# tritiled22_cr2354_lux_c.net
KiCad netlist of a schematic drawn in EAGLE
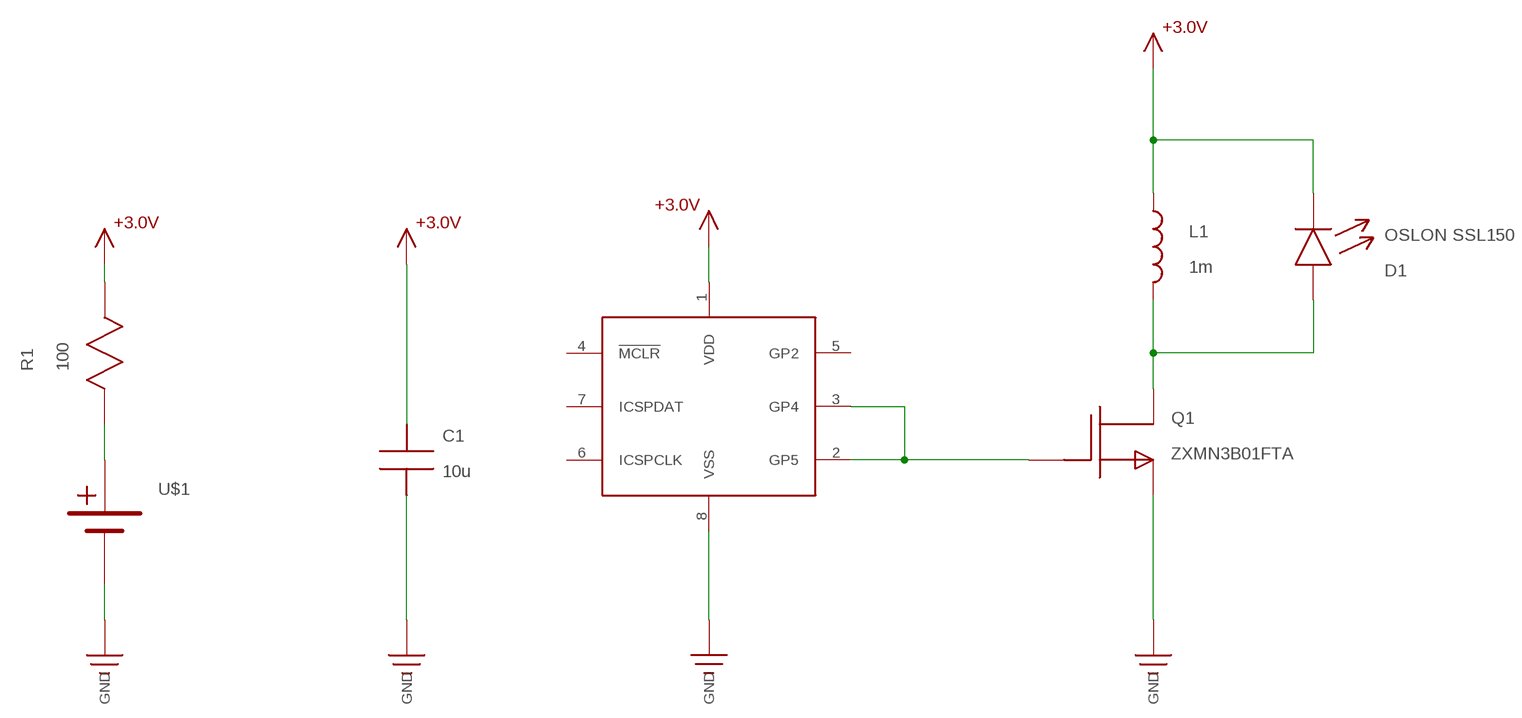
[diagram p0: schematic, sheet 1]

(export (version "E")
  (design (tool "Eeschema 10.0.6"))
  (components
    (comp (ref "C1")
      (value "10u")
      (footprint "eagle-import:1206")
      (libsource (lib "eagle-import") (part "C1206"))
    )
    (comp (ref "D1")
      (value "OSLON SSL150")
      (footprint "eagle-import:LUXEON_C")
      (libsource (lib "eagle-import") (part "LEDLUXEON_C"))
    )
    (comp (ref "L1")
      (value "1m")
      (footprint "eagle-import:SRR6028_INDUCTOR")
      (libsource (lib "eagle-import") (part "SRR6028_INDUCTOR"))
    )
    (comp (ref "Q1")
      (value "ZXMN3B01FTA")
      (footprint "eagle-import:SOT-23")
      (libsource (lib "eagle-import") (part "ZXMN3B01FSOT23"))
    )
    (comp (ref "R1")
      (value "100")
      (footprint "eagle-import:R1206")
      (libsource (lib "eagle-import") (part "R1206"))
    )
    (comp (ref "U$1")
      (value "CR2354_TABBED")
      (footprint "eagle-import:CR2354_TABBED")
      (libsource (lib "eagle-import") (part "CR2354_TABBED"))
    )
    (comp (ref "U1")
      (value "PIC12LF1571")
      (footprint "eagle-import:SOIC8")
      (libsource (lib "eagle-import") (part "PIC12LF1571"))
    )
  )
  (nets
    (net (code "1") (name "+3.0V") (class "Default")
      (node (ref "C1") (pin "P$1") (pinfunction "P$1_P$1") (pintype "bidirectional"))
      (node (ref "D1") (pin "C") (pinfunction "C_C") (pintype "bidirectional"))
      (node (ref "L1") (pin "P$1") (pinfunction "1_P$1") (pintype "passive"))
      (node (ref "R1") (pin "P$2") (pinfunction "P$2_P$2") (pintype "bidirectional"))
      (node (ref "U1") (pin "1") (pinfunction "VDD_1") (pintype "bidirectional"))
    )
    (net (code "2") (name "GND") (class "Default")
      (node (ref "C1") (pin "P$2") (pinfunction "P$2_P$2") (pintype "bidirectional"))
      (node (ref "Q1") (pin "2") (pinfunction "S_2") (pintype "bidirectional"))
      (node (ref "U$1") (pin "GND") (pinfunction "0V_GND") (pintype "power_in"))
      (node (ref "U1") (pin "8") (pinfunction "VSS_8") (pintype "bidirectional"))
    )
    (net (code "3") (name "Net-(L1-2)") (class "Default")
      (node (ref "D1") (pin "A") (pinfunction "A_A") (pintype "bidirectional"))
      (node (ref "L1") (pin "P$2") (pinfunction "2_P$2") (pintype "passive"))
      (node (ref "Q1") (pin "3") (pinfunction "D_3") (pintype "bidirectional"))
    )
    (net (code "4") (name "Net-(Q1-G)") (class "Default")
      (node (ref "Q1") (pin "1") (pinfunction "G_1") (pintype "bidirectional"))
      (node (ref "U1") (pin "2") (pinfunction "GP5_2") (pintype "bidirectional"))
      (node (ref "U1") (pin "3") (pinfunction "GP4_3") (pintype "bidirectional"))
    )
    (net (code "5") (name "Net-(U$1-+V)") (class "Default")
      (node (ref "R1") (pin "P$1") (pinfunction "P$1_P$1") (pintype "bidirectional"))
      (node (ref "U$1") (pin "+3V") (pinfunction "+V_+3V") (pintype "power_in"))
    )
    (net (code "6") (name "unconnected-(U1-GP2-Pad5)") (class "Default")
      (node (ref "U1") (pin "5") (pinfunction "GP2_5") (pintype "bidirectional"))
    )
    (net (code "7") (name "unconnected-(U1-ICSPCLK-Pad6)") (class "Default")
      (node (ref "U1") (pin "6") (pinfunction "ICSPCLK_6") (pintype "bidirectional"))
    )
    (net (code "8") (name "unconnected-(U1-ICSPDAT-Pad7)") (class "Default")
      (node (ref "U1") (pin "7") (pinfunction "ICSPDAT_7") (pintype "bidirectional"))
    )
    (net (code "9") (name "unconnected-(U1-~{MCLR}-Pad4)") (class "Default")
      (node (ref "U1") (pin "4") (pinfunction "~{MCLR}_4") (pintype "bidirectional"))
    )
  )
)
